# CAA-NMC.net
KiCad netlist of a schematic drawn in EAGLE
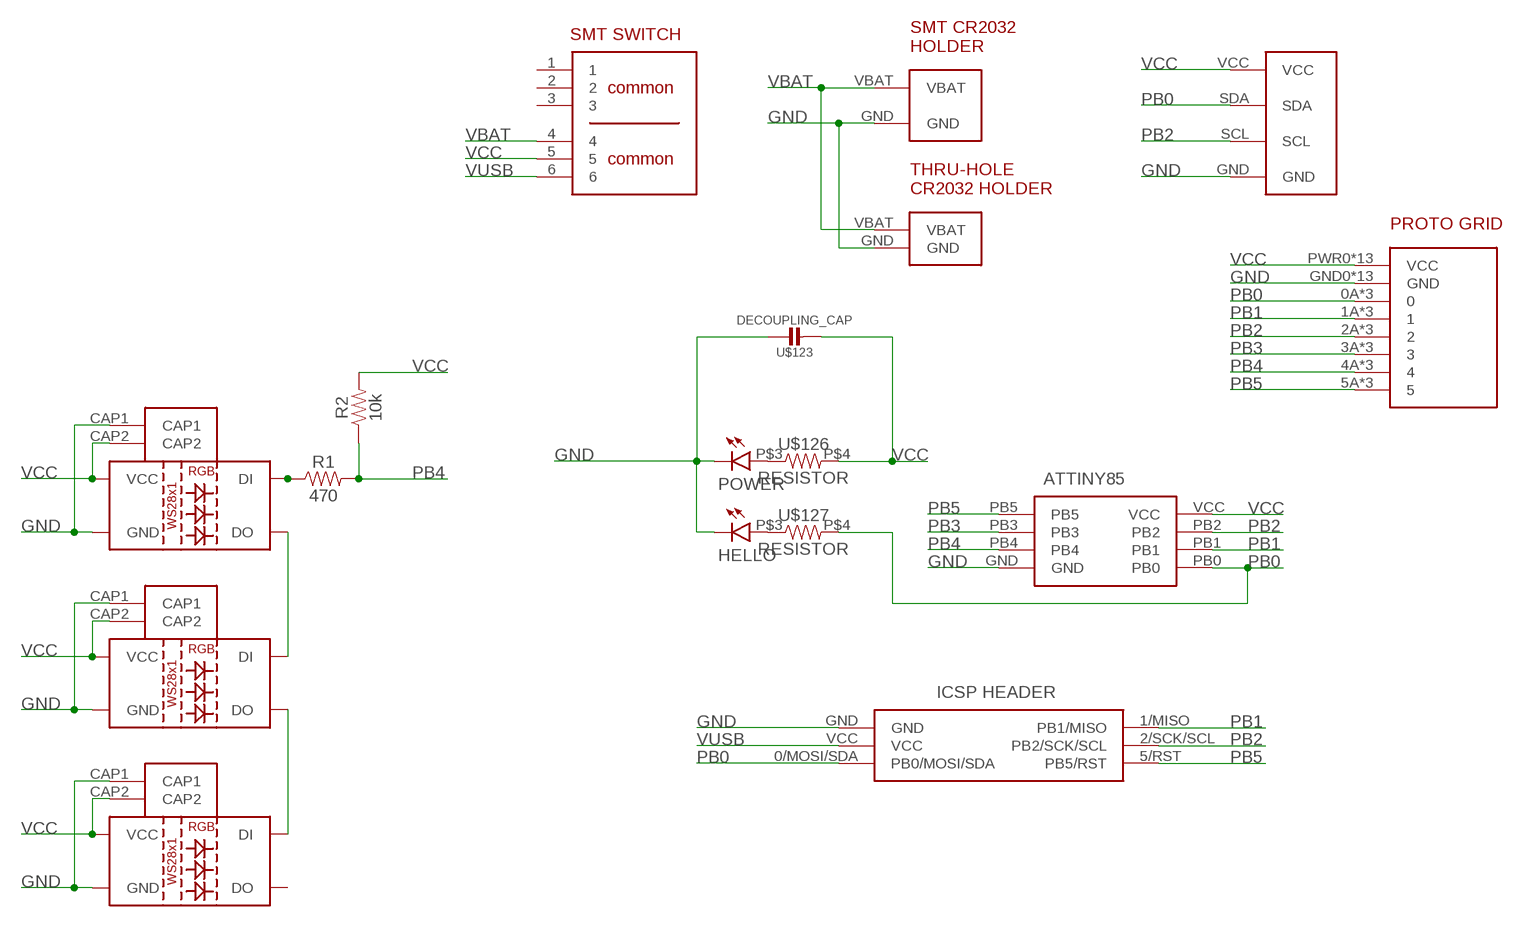
[diagram p0: schematic, sheet 1]

(export (version "E")
  (design (tool "Eeschema 10.0.6"))
  (components
    (comp (ref "D1")
      (value "WS2812B")
      (footprint "eagle-import:WS2812B")
      (libsource (lib "eagle-import") (part "WS2812B"))
    )
    (comp (ref "D2")
      (value "WS2812B")
      (footprint "eagle-import:WS2812B")
      (libsource (lib "eagle-import") (part "WS2812B"))
    )
    (comp (ref "D3")
      (value "WS2812B")
      (footprint "eagle-import:WS2812B")
      (libsource (lib "eagle-import") (part "WS2812B"))
    )
    (comp (ref "HELLO")
      (value "LED3MM")
      (footprint "eagle-import:LED3MM")
      (libsource (lib "eagle-import") (part "LED3MM"))
    )
    (comp (ref "IC1")
      (value "ATTINY85-20SU")
      (footprint "eagle-import:SOT127P798X216-8N")
      (fields (field (name "RS_PART_NUMBER") "1331674"))
      (libsource (lib "eagle-import") (part "ATTINY85-20SU"))
    )
    (comp (ref "J1")
      (value "M20-9980346")
      (footprint "eagle-import:HDRV6W64P254_2X3_762X508X868P")
      (fields (field (name "RS_PART_NUMBER") "7457046P"))
      (libsource (lib "eagle-import") (part "M20-9980346"))
    )
    (comp (ref "POWER")
      (value "LED3MM")
      (footprint "eagle-import:LED3MM")
      (libsource (lib "eagle-import") (part "LED3MM"))
    )
    (comp (ref "R1")
      (value "470")
      (footprint "eagle-import:0603")
      (libsource (lib "eagle-import") (part "470OHM-0603-1/10W-1%"))
    )
    (comp (ref "R2")
      (value "10k")
      (footprint "eagle-import:0603")
      (libsource (lib "eagle-import") (part "10KOHM-0603-1/10W-1%"))
    )
    (comp (ref "U$1")
      (value "PROTO")
      (footprint "eagle-import:PROTO")
      (libsource (lib "eagle-import") (part "PROTO"))
    )
    (comp (ref "U$2")
      (value "SMT-BATTERY-HOLDER")
      (footprint "eagle-import:SMT-CR-HOLDER")
      (libsource (lib "eagle-import") (part "SMT-BATTERY-HOLDER"))
    )
    (comp (ref "U$3")
      (value "THRU-CR-HOLDER")
      (footprint "eagle-import:THRU-CR-HOLDER")
      (libsource (lib "eagle-import") (part "THRU-CR-HOLDER"))
    )
    (comp (ref "U$4")
      (value "I2C-PADS")
      (footprint "eagle-import:I2C-PADS")
      (libsource (lib "eagle-import") (part "I2C-PADS"))
    )
    (comp (ref "U$123")
      (value "DECOUPLING_CAP")
      (footprint "eagle-import:DECOUPLING_CAP")
      (libsource (lib "eagle-import") (part "DECOUPLING_CAP"))
    )
    (comp (ref "U$126")
      (value "RESISTOR")
      (footprint "eagle-import:AXIAL-0.3")
      (libsource (lib "eagle-import") (part "RESISTOR"))
    )
    (comp (ref "U$127")
      (value "RESISTOR")
      (footprint "eagle-import:AXIAL-0.3")
      (libsource (lib "eagle-import") (part "RESISTOR"))
    )
    (comp (ref "U$145")
      (value "SMT-SWITCH")
      (footprint "eagle-import:SMT-SWITCH")
      (libsource (lib "eagle-import") (part "SMT-SWITCH"))
    )
  )
  (nets
    (net (code "1") (name "/GND") (class "Default")
      (node (ref "D1") (pin "CAP1") (pinfunction "CAP1_CAP1") (pintype "bidirectional"))
      (node (ref "D1") (pin "GND") (pinfunction "GND_GND") (pintype "bidirectional"))
      (node (ref "D2") (pin "CAP1") (pinfunction "CAP1_CAP1") (pintype "bidirectional"))
      (node (ref "D2") (pin "GND") (pinfunction "GND_GND") (pintype "bidirectional"))
      (node (ref "D3") (pin "CAP1") (pinfunction "CAP1_CAP1") (pintype "bidirectional"))
      (node (ref "D3") (pin "GND") (pinfunction "GND_GND") (pintype "bidirectional"))
      (node (ref "HELLO") (pin "NEG") (pinfunction "NEG_NEG") (pintype "passive"))
      (node (ref "IC1") (pin "GND") (pinfunction "GND_GND") (pintype "bidirectional"))
      (node (ref "J1") (pin "GND") (pinfunction "GND_GND") (pintype "bidirectional"))
      (node (ref "POWER") (pin "NEG") (pinfunction "NEG_NEG") (pintype "passive"))
      (node (ref "U$1") (pin "GND0") (pinfunction "GND_GND0") (pintype "bidirectional"))
      (node (ref "U$1") (pin "GND1") (pinfunction "GND_GND1") (pintype "bidirectional"))
      (node (ref "U$1") (pin "GND10") (pinfunction "GND_GND10") (pintype "bidirectional"))
      (node (ref "U$1") (pin "GND11") (pinfunction "GND_GND11") (pintype "bidirectional"))
      (node (ref "U$1") (pin "GND12") (pinfunction "GND_GND12") (pintype "bidirectional"))
      (node (ref "U$1") (pin "GND2") (pinfunction "GND_GND2") (pintype "bidirectional"))
      (node (ref "U$1") (pin "GND3") (pinfunction "GND_GND3") (pintype "bidirectional"))
      (node (ref "U$1") (pin "GND4") (pinfunction "GND_GND4") (pintype "bidirectional"))
      (node (ref "U$1") (pin "GND5") (pinfunction "GND_GND5") (pintype "bidirectional"))
      (node (ref "U$1") (pin "GND6") (pinfunction "GND_GND6") (pintype "bidirectional"))
      (node (ref "U$1") (pin "GND7") (pinfunction "GND_GND7") (pintype "bidirectional"))
      (node (ref "U$1") (pin "GND8") (pinfunction "GND_GND8") (pintype "bidirectional"))
      (node (ref "U$1") (pin "GND9") (pinfunction "GND_GND9") (pintype "bidirectional"))
      (node (ref "U$123") (pin "P$1") (pinfunction "1_P$1") (pintype "passive"))
      (node (ref "U$2") (pin "GND") (pinfunction "GND_GND") (pintype "bidirectional"))
      (node (ref "U$3") (pin "GND") (pinfunction "GND_GND") (pintype "bidirectional"))
      (node (ref "U$4") (pin "GND") (pinfunction "GND_GND") (pintype "bidirectional"))
    )
    (net (code "2") (name "/PB0") (class "Default")
      (node (ref "IC1") (pin "PB0") (pinfunction "PB0_PB0") (pintype "bidirectional"))
      (node (ref "J1") (pin "0/MOSI/SDA") (pinfunction "PB0/MOSI/SDA_0/MOSI/SDA") (pintype "bidirectional"))
      (node (ref "U$1") (pin "0A") (pinfunction "0_0A") (pintype "bidirectional"))
      (node (ref "U$1") (pin "0B") (pinfunction "0_0B") (pintype "bidirectional"))
      (node (ref "U$1") (pin "0C") (pinfunction "0_0C") (pintype "bidirectional"))
      (node (ref "U$127") (pin "P$4") (pinfunction "2_P$4") (pintype "passive"))
      (node (ref "U$4") (pin "SDA") (pinfunction "SDA_SDA") (pintype "bidirectional"))
    )
    (net (code "3") (name "/PB1") (class "Default")
      (node (ref "IC1") (pin "PB1") (pinfunction "PB1_PB1") (pintype "bidirectional"))
      (node (ref "J1") (pin "1/MISO") (pinfunction "PB1/MISO_1/MISO") (pintype "bidirectional"))
      (node (ref "U$1") (pin "1A") (pinfunction "1_1A") (pintype "bidirectional"))
      (node (ref "U$1") (pin "1B") (pinfunction "1_1B") (pintype "bidirectional"))
      (node (ref "U$1") (pin "1C") (pinfunction "1_1C") (pintype "bidirectional"))
    )
    (net (code "4") (name "/PB2") (class "Default")
      (node (ref "IC1") (pin "PB2") (pinfunction "PB2_PB2") (pintype "bidirectional"))
      (node (ref "J1") (pin "2/SCK/SCL") (pinfunction "PB2/SCK/SCL_2/SCK/SCL") (pintype "bidirectional"))
      (node (ref "U$1") (pin "2A") (pinfunction "2_2A") (pintype "bidirectional"))
      (node (ref "U$1") (pin "2B") (pinfunction "2_2B") (pintype "bidirectional"))
      (node (ref "U$1") (pin "2C") (pinfunction "2_2C") (pintype "bidirectional"))
      (node (ref "U$4") (pin "SCL") (pinfunction "SCL_SCL") (pintype "bidirectional"))
    )
    (net (code "5") (name "/PB3") (class "Default")
      (node (ref "IC1") (pin "PB3") (pinfunction "PB3_PB3") (pintype "bidirectional"))
      (node (ref "U$1") (pin "3A") (pinfunction "3_3A") (pintype "bidirectional"))
      (node (ref "U$1") (pin "3B") (pinfunction "3_3B") (pintype "bidirectional"))
      (node (ref "U$1") (pin "3C") (pinfunction "3_3C") (pintype "bidirectional"))
    )
    (net (code "6") (name "/PB4") (class "Default")
      (node (ref "IC1") (pin "PB4") (pinfunction "PB4_PB4") (pintype "bidirectional"))
      (node (ref "R1") (pin "2") (pinfunction "2_2") (pintype "passive"))
      (node (ref "R2") (pin "1") (pinfunction "1_1") (pintype "passive"))
      (node (ref "U$1") (pin "4A") (pinfunction "4_4A") (pintype "bidirectional"))
      (node (ref "U$1") (pin "4B") (pinfunction "4_4B") (pintype "bidirectional"))
      (node (ref "U$1") (pin "4C") (pinfunction "4_4C") (pintype "bidirectional"))
    )
    (net (code "7") (name "/PB5") (class "Default")
      (node (ref "IC1") (pin "PB5") (pinfunction "PB5_PB5") (pintype "bidirectional"))
      (node (ref "J1") (pin "5/RST") (pinfunction "PB5/RST_5/RST") (pintype "bidirectional"))
      (node (ref "U$1") (pin "5A") (pinfunction "5_5A") (pintype "bidirectional"))
      (node (ref "U$1") (pin "5B") (pinfunction "5_5B") (pintype "bidirectional"))
      (node (ref "U$1") (pin "5C") (pinfunction "5_5C") (pintype "bidirectional"))
    )
    (net (code "8") (name "/VBAT") (class "Default")
      (node (ref "U$145") (pin "4") (pinfunction "4_4") (pintype "bidirectional"))
      (node (ref "U$2") (pin "VBAT") (pinfunction "VBAT_VBAT") (pintype "bidirectional"))
      (node (ref "U$3") (pin "VBAT") (pinfunction "VBAT_VBAT") (pintype "bidirectional"))
    )
    (net (code "9") (name "/VCC") (class "Default")
      (node (ref "D1") (pin "CAP2") (pinfunction "CAP2_CAP2") (pintype "bidirectional"))
      (node (ref "D1") (pin "VCC") (pinfunction "VCC_VCC") (pintype "bidirectional"))
      (node (ref "D2") (pin "CAP2") (pinfunction "CAP2_CAP2") (pintype "bidirectional"))
      (node (ref "D2") (pin "VCC") (pinfunction "VCC_VCC") (pintype "bidirectional"))
      (node (ref "D3") (pin "CAP2") (pinfunction "CAP2_CAP2") (pintype "bidirectional"))
      (node (ref "D3") (pin "VCC") (pinfunction "VCC_VCC") (pintype "bidirectional"))
      (node (ref "IC1") (pin "VCC") (pinfunction "VCC_VCC") (pintype "bidirectional"))
      (node (ref "R2") (pin "2") (pinfunction "2_2") (pintype "passive"))
      (node (ref "U$1") (pin "PWR0") (pinfunction "VCC_PWR0") (pintype "bidirectional"))
      (node (ref "U$1") (pin "PWR1") (pinfunction "VCC_PWR1") (pintype "bidirectional"))
      (node (ref "U$1") (pin "PWR10") (pinfunction "VCC_PWR10") (pintype "bidirectional"))
      (node (ref "U$1") (pin "PWR11") (pinfunction "VCC_PWR11") (pintype "bidirectional"))
      (node (ref "U$1") (pin "PWR12") (pinfunction "VCC_PWR12") (pintype "bidirectional"))
      (node (ref "U$1") (pin "PWR2") (pinfunction "VCC_PWR2") (pintype "bidirectional"))
      (node (ref "U$1") (pin "PWR3") (pinfunction "VCC_PWR3") (pintype "bidirectional"))
      (node (ref "U$1") (pin "PWR4") (pinfunction "VCC_PWR4") (pintype "bidirectional"))
      (node (ref "U$1") (pin "PWR5") (pinfunction "VCC_PWR5") (pintype "bidirectional"))
      (node (ref "U$1") (pin "PWR6") (pinfunction "VCC_PWR6") (pintype "bidirectional"))
      (node (ref "U$1") (pin "PWR7") (pinfunction "VCC_PWR7") (pintype "bidirectional"))
      (node (ref "U$1") (pin "PWR8") (pinfunction "VCC_PWR8") (pintype "bidirectional"))
      (node (ref "U$1") (pin "PWR9") (pinfunction "VCC_PWR9") (pintype "bidirectional"))
      (node (ref "U$123") (pin "P$2") (pinfunction "2_P$2") (pintype "passive"))
      (node (ref "U$126") (pin "P$4") (pinfunction "2_P$4") (pintype "passive"))
      (node (ref "U$145") (pin "5") (pinfunction "5_5") (pintype "bidirectional"))
      (node (ref "U$4") (pin "VCC") (pinfunction "VCC_VCC") (pintype "bidirectional"))
    )
    (net (code "10") (name "/VUSB") (class "Default")
      (node (ref "J1") (pin "VCC") (pinfunction "VCC_VCC") (pintype "bidirectional"))
      (node (ref "U$145") (pin "6") (pinfunction "6_6") (pintype "bidirectional"))
    )
    (net (code "11") (name "Net-(D1-PadDI)") (class "Default")
      (node (ref "D1") (pin "DI") (pinfunction "DI_DI") (pintype "bidirectional"))
      (node (ref "R1") (pin "1") (pinfunction "1_1") (pintype "passive"))
    )
    (net (code "12") (name "Net-(D1-PadDO)") (class "Default")
      (node (ref "D1") (pin "DO") (pinfunction "DO_DO") (pintype "bidirectional"))
      (node (ref "D2") (pin "DI") (pinfunction "DI_DI") (pintype "bidirectional"))
    )
    (net (code "13") (name "Net-(D2-PadDO)") (class "Default")
      (node (ref "D2") (pin "DO") (pinfunction "DO_DO") (pintype "bidirectional"))
      (node (ref "D3") (pin "DI") (pinfunction "DI_DI") (pintype "bidirectional"))
    )
    (net (code "14") (name "Net-(U$126-1)") (class "Default")
      (node (ref "POWER") (pin "POS") (pinfunction "POS_POS") (pintype "passive"))
      (node (ref "U$126") (pin "P$3") (pinfunction "1_P$3") (pintype "passive"))
    )
    (net (code "15") (name "Net-(U$127-1)") (class "Default")
      (node (ref "HELLO") (pin "POS") (pinfunction "POS_POS") (pintype "passive"))
      (node (ref "U$127") (pin "P$3") (pinfunction "1_P$3") (pintype "passive"))
    )
    (net (code "16") (name "unconnected-(D3-PadDO)") (class "Default")
      (node (ref "D3") (pin "DO") (pinfunction "DO_DO") (pintype "bidirectional"))
    )
    (net (code "17") (name "unconnected-(U$145-Pad1)") (class "Default")
      (node (ref "U$145") (pin "1") (pinfunction "1_1") (pintype "bidirectional"))
    )
    (net (code "18") (name "unconnected-(U$145-Pad2)") (class "Default")
      (node (ref "U$145") (pin "2") (pinfunction "2_2") (pintype "bidirectional"))
    )
    (net (code "19") (name "unconnected-(U$145-Pad3)") (class "Default")
      (node (ref "U$145") (pin "3") (pinfunction "3_3") (pintype "bidirectional"))
    )
  )
)
